# Digital.net
KiCad netlist of a schematic drawn in Altium Designer
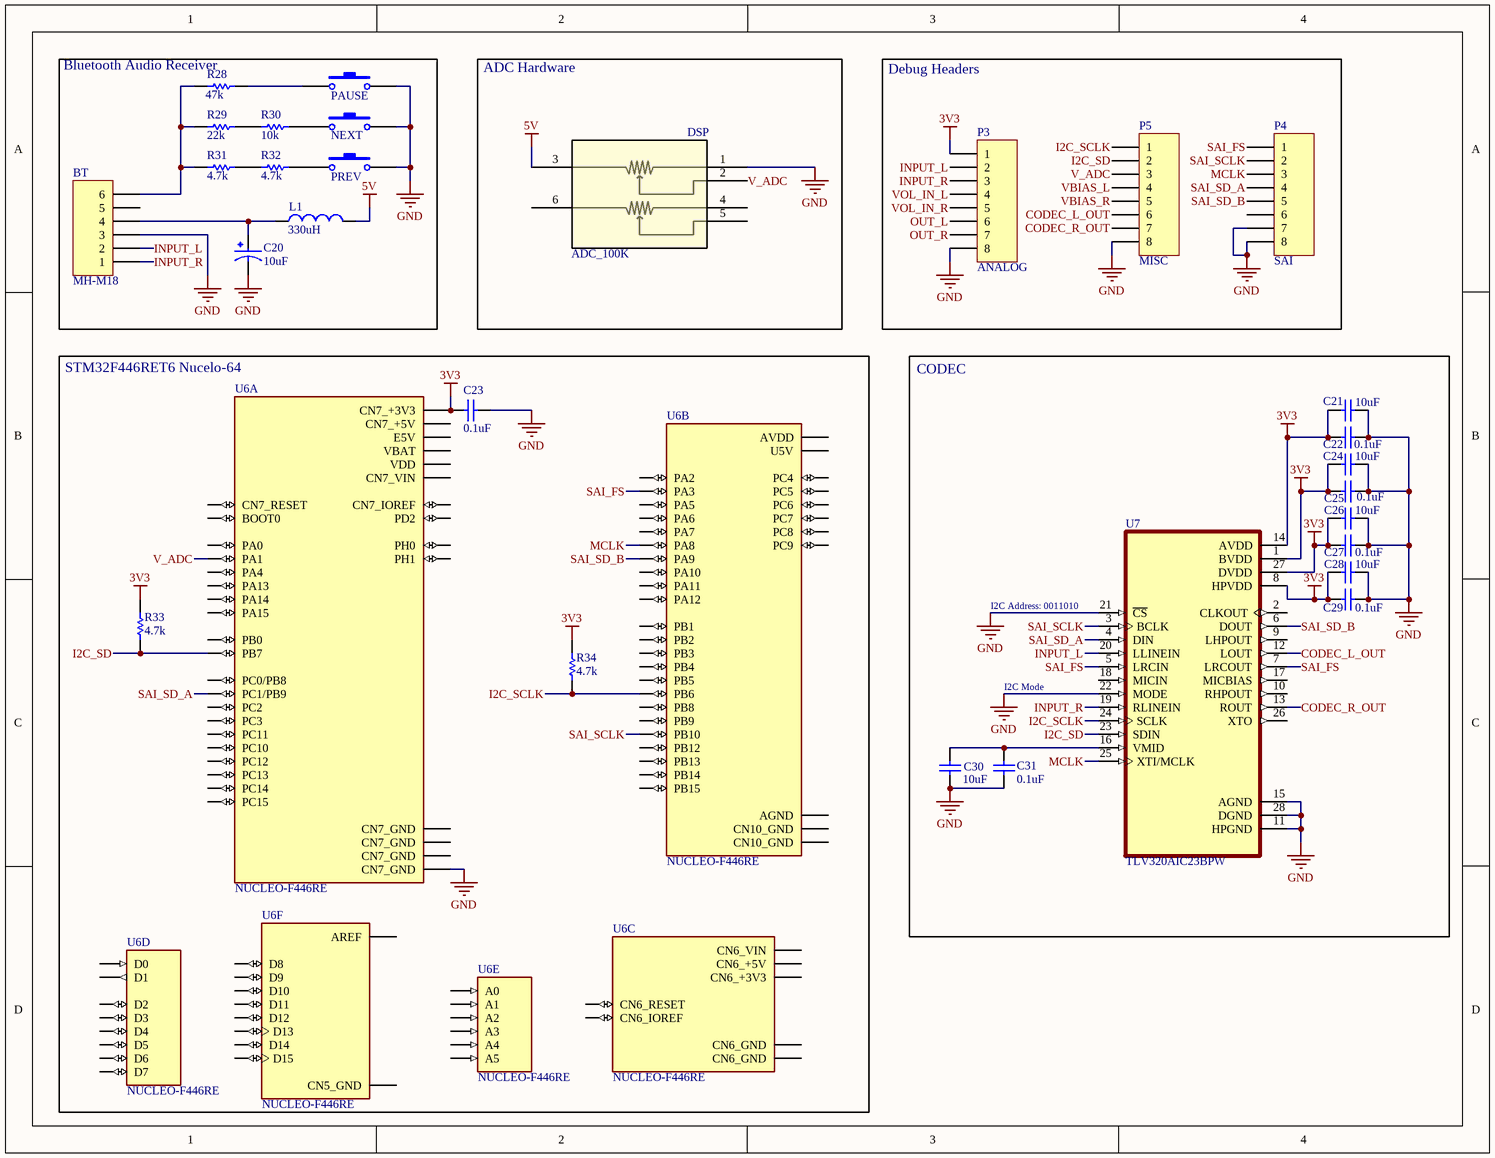
[diagram p0: Digital.SchDoc]

(export (version "E")
  (design (tool "Eeschema 10.0.6"))
  (components
    (comp (ref "BT")
      (value "MH-M18")
      (footprint "HDR1X6")
      (description "Header, 6-Pin")
      (fields (field (name "PUBLISHER") "Altium Limited"))
      (libsource (lib "Miscellaneous Connectors") (part "Header 6"))
    )
    (comp (ref "C20")
      (value "10uF")
      (footprint "CAPPRD200W50D500H1500")
      (description "Capacitor; Aluminum Electrolytic; Radial Al Electrolytic Cap; 100uF 63V")
      (fields (field (name "MF") "Panasonic Electronic") (field (name "MP") "EEU-FC1J101"))
      (libsource (lib "EEUFC1J101") (part "EEUFC1J101"))
    )
    (comp (ref "C21")
      (value "10uF")
      (footprint "RAD-0.1")
      (description "Capacitor")
      (fields (field (name "Comment") "Cap") (field (name "PUBLISHER") "Altium Limited"))
      (libsource (lib "Miscellaneous Devices") (part "Cap"))
    )
    (comp (ref "C22")
      (value "0.1uF")
      (footprint "RAD-0.1")
      (description "Capacitor")
      (fields (field (name "Comment") "Cap") (field (name "PUBLISHER") "Altium Limited"))
      (libsource (lib "Miscellaneous Devices") (part "Cap"))
    )
    (comp (ref "C23")
      (value "0.1uF")
      (footprint "RAD-0.1")
      (description "Capacitor")
      (fields (field (name "Comment") "Cap") (field (name "PUBLISHER") "Altium Limited"))
      (libsource (lib "Miscellaneous Devices") (part "Cap"))
    )
    (comp (ref "C24")
      (value "10uF")
      (footprint "RAD-0.1")
      (description "Capacitor")
      (fields (field (name "Comment") "Cap") (field (name "PUBLISHER") "Altium Limited"))
      (libsource (lib "Miscellaneous Devices") (part "Cap"))
    )
    (comp (ref "C25")
      (value "0.1uF")
      (footprint "RAD-0.1")
      (description "Capacitor")
      (fields (field (name "Comment") "Cap") (field (name "PUBLISHER") "Altium Limited"))
      (libsource (lib "Miscellaneous Devices") (part "Cap"))
    )
    (comp (ref "C26")
      (value "10uF")
      (footprint "RAD-0.1")
      (description "Capacitor")
      (fields (field (name "Comment") "Cap") (field (name "PUBLISHER") "Altium Limited"))
      (libsource (lib "Miscellaneous Devices") (part "Cap"))
    )
    (comp (ref "C27")
      (value "0.1uF")
      (footprint "RAD-0.1")
      (description "Capacitor")
      (fields (field (name "Comment") "Cap") (field (name "PUBLISHER") "Altium Limited"))
      (libsource (lib "Miscellaneous Devices") (part "Cap"))
    )
    (comp (ref "C28")
      (value "10uF")
      (footprint "RAD-0.1")
      (description "Capacitor")
      (fields (field (name "Comment") "Cap") (field (name "PUBLISHER") "Altium Limited"))
      (libsource (lib "Miscellaneous Devices") (part "Cap"))
    )
    (comp (ref "C29")
      (value "0.1uF")
      (footprint "RAD-0.1")
      (description "Capacitor")
      (fields (field (name "Comment") "Cap") (field (name "PUBLISHER") "Altium Limited"))
      (libsource (lib "Miscellaneous Devices") (part "Cap"))
    )
    (comp (ref "C30")
      (value "10uF")
      (footprint "RAD-0.1")
      (description "Capacitor")
      (fields (field (name "Comment") "Cap") (field (name "PUBLISHER") "Altium Limited"))
      (libsource (lib "Miscellaneous Devices") (part "Cap"))
    )
    (comp (ref "C31")
      (value "0.1uF")
      (footprint "RAD-0.1")
      (description "Capacitor")
      (fields (field (name "Comment") "Cap") (field (name "PUBLISHER") "Altium Limited"))
      (libsource (lib "Miscellaneous Devices") (part "Cap"))
    )
    (comp (ref "DSP")
      (value "ADC_100K")
      (footprint "Bourns_PDB182-K425K-103A_0")
      (description "No Description Available")
      (fields
        (field (name "MANUFACTURER_PART_NUMBER") "PDB182-K420K-103A2")
        (field (name "COPYRIGHT") "Copyright (C) 2022 Ultra Librarian. All rights reserved.")
      )
      (libsource (lib "PDB182-K420K-103A2") (part "PDB182-K420K-103A2"))
    )
    (comp (ref "L1")
      (value "330uH")
      (footprint "RAD-0.4")
      (description "Inductor")
      (fields (field (name "PUBLISHER") "Altium Limited"))
      (libsource (lib "Miscellaneous Devices") (part "Inductor"))
    )
    (comp (ref "NEXT")
      (value "NEXT")
      (footprint "SW PB")
      (description "Switch")
      (fields (field (name "PUBLISHER") "Altium Limited"))
      (libsource (lib "Miscellaneous Devices") (part "SW-PB"))
    )
    (comp (ref "P3")
      (value "ANALOG")
      (footprint "HDR1X8")
      (description "Header, 8-Pin")
      (fields (field (name "PUBLISHER") "Altium Limited"))
      (libsource (lib "Miscellaneous Connectors") (part "Header 8"))
    )
    (comp (ref "P4")
      (value "SAI")
      (footprint "HDR1X8")
      (description "Header, 8-Pin")
      (fields (field (name "PUBLISHER") "Altium Limited"))
      (libsource (lib "Miscellaneous Connectors") (part "Header 8"))
    )
    (comp (ref "P5")
      (value "MISC")
      (footprint "HDR1X8")
      (description "Header, 8-Pin")
      (fields (field (name "PUBLISHER") "Altium Limited"))
      (libsource (lib "Miscellaneous Connectors") (part "Header 8"))
    )
    (comp (ref "PAUSE")
      (value "PAUSE")
      (footprint "SW PB")
      (description "Switch")
      (fields (field (name "PUBLISHER") "Altium Limited"))
      (libsource (lib "Miscellaneous Devices") (part "SW-PB"))
    )
    (comp (ref "PREV")
      (value "PREV")
      (footprint "SW PB")
      (description "Switch")
      (fields (field (name "PUBLISHER") "Altium Limited"))
      (libsource (lib "Miscellaneous Devices") (part "SW-PB"))
    )
    (comp (ref "R28")
      (value "47k")
      (footprint "AXIAL-0.3")
      (description "Resistor")
      (fields (field (name "Comment") "Res1") (field (name "PUBLISHER") "Altium Limited"))
      (libsource (lib "Miscellaneous Devices") (part "Res1"))
    )
    (comp (ref "R29")
      (value "22k")
      (footprint "AXIAL-0.3")
      (description "Resistor")
      (fields (field (name "Comment") "Res1") (field (name "PUBLISHER") "Altium Limited"))
      (libsource (lib "Miscellaneous Devices") (part "Res1"))
    )
    (comp (ref "R30")
      (value "10k")
      (footprint "AXIAL-0.3")
      (description "Resistor")
      (fields (field (name "Comment") "Res1") (field (name "PUBLISHER") "Altium Limited"))
      (libsource (lib "Miscellaneous Devices") (part "Res1"))
    )
    (comp (ref "R31")
      (value "4.7k")
      (footprint "AXIAL-0.3")
      (description "Resistor")
      (fields (field (name "Comment") "Res1") (field (name "PUBLISHER") "Altium Limited"))
      (libsource (lib "Miscellaneous Devices") (part "Res1"))
    )
    (comp (ref "R32")
      (value "4.7k")
      (footprint "AXIAL-0.3")
      (description "Resistor")
      (fields (field (name "Comment") "Res1") (field (name "PUBLISHER") "Altium Limited"))
      (libsource (lib "Miscellaneous Devices") (part "Res1"))
    )
    (comp (ref "R33")
      (value "4.7k")
      (footprint "AXIAL-0.3")
      (description "Resistor")
      (fields (field (name "Comment") "Res1") (field (name "PUBLISHER") "Altium Limited"))
      (libsource (lib "Miscellaneous Devices") (part "Res1"))
    )
    (comp (ref "R34")
      (value "4.7k")
      (footprint "AXIAL-0.3")
      (description "Resistor")
      (fields (field (name "Comment") "Res1") (field (name "PUBLISHER") "Altium Limited"))
      (libsource (lib "Miscellaneous Devices") (part "Res1"))
    )
    (comp (ref "U6")
      (value "NUCLEO-F446RE")
      (footprint "MODULE_NUCLEO-F446RE")
      (libsource (lib "NUCLEO-F446RE") (part "NUCLEO-F446RE"))
    )
    (comp (ref "U7")
      (value "TLV320AIC23BPW")
      (footprint "SOP65P640X120-28N")
      (description "Low-Power Stereo CODEC with HP Amplifier 28-TSSOP -10 to 70")
      (fields (field (name "MF") "Texas Instruments"))
      (libsource (lib "TLV320AIC23BPW") (part "TLV320AIC23BPW"))
    )
  )
  (nets
    (net (code "1") (name "/CODEC_L_OUT") (class "Default")
      (node (ref "P5") (pin "6") (pinfunction "6_6") (pintype "passive"))
      (node (ref "U7") (pin "12") (pinfunction "LOUT_12") (pintype "output"))
    )
    (net (code "2") (name "/CODEC_R_OUT") (class "Default")
      (node (ref "P5") (pin "7") (pinfunction "7_7") (pintype "passive"))
      (node (ref "U7") (pin "13") (pinfunction "ROUT_13") (pintype "output"))
    )
    (net (code "3") (name "/I2C_SCLK") (class "Default")
      (node (ref "P5") (pin "1") (pinfunction "1_1") (pintype "passive"))
      (node (ref "R34") (pin "1") (pinfunction "1_1") (pintype "passive"))
      (node (ref "U6") (pin "CN10_17") (pinfunction "PB6_CN10_17") (pintype "bidirectional"))
      (node (ref "U7") (pin "24") (pinfunction "SCLK_24") (pintype "input"))
    )
    (net (code "4") (name "/I2C_SD") (class "Default")
      (node (ref "P5") (pin "2") (pinfunction "2_2") (pintype "passive"))
      (node (ref "R33") (pin "1") (pinfunction "1_1") (pintype "passive"))
      (node (ref "U6") (pin "CN7_21") (pinfunction "PB7_CN7_21") (pintype "bidirectional"))
      (node (ref "U7") (pin "23") (pinfunction "SDIN_23") (pintype "input"))
    )
    (net (code "5") (name "/INPUT_L") (class "Default")
      (node (ref "BT") (pin "2") (pinfunction "2_2") (pintype "passive"))
      (node (ref "P3") (pin "2") (pinfunction "2_2") (pintype "passive"))
      (node (ref "U7") (pin "20") (pinfunction "LLINEIN_20") (pintype "input"))
    )
    (net (code "6") (name "/INPUT_R") (class "Default")
      (node (ref "BT") (pin "1") (pinfunction "1_1") (pintype "passive"))
      (node (ref "P3") (pin "3") (pinfunction "3_3") (pintype "passive"))
      (node (ref "U7") (pin "19") (pinfunction "RLINEIN_19") (pintype "input"))
    )
    (net (code "7") (name "/MCLK") (class "Default")
      (node (ref "P4") (pin "3") (pinfunction "3_3") (pintype "passive"))
      (node (ref "U6") (pin "CN10_23") (pinfunction "PA8_CN10_23") (pintype "bidirectional"))
      (node (ref "U7") (pin "25") (pinfunction "XTI/MCLK_25") (pintype "input"))
    )
    (net (code "8") (name "/OUT_L") (class "Default")
      (node (ref "P3") (pin "6") (pinfunction "6_6") (pintype "passive"))
    )
    (net (code "9") (name "/OUT_R") (class "Default")
      (node (ref "P3") (pin "7") (pinfunction "7_7") (pintype "passive"))
    )
    (net (code "10") (name "/SAI_FS") (class "Default")
      (node (ref "P4") (pin "1") (pinfunction "1_1") (pintype "passive"))
      (node (ref "U6") (pin "CN10_37") (pinfunction "PA3_CN10_37") (pintype "bidirectional"))
      (node (ref "U7") (pin "5") (pinfunction "LRCIN_5") (pintype "input"))
      (node (ref "U7") (pin "7") (pinfunction "LRCOUT_7") (pintype "output"))
    )
    (net (code "11") (name "/SAI_SCLK") (class "Default")
      (node (ref "P4") (pin "2") (pinfunction "2_2") (pintype "passive"))
      (node (ref "U6") (pin "CN10_25") (pinfunction "PB10_CN10_25") (pintype "bidirectional"))
      (node (ref "U7") (pin "3") (pinfunction "BCLK_3") (pintype "input"))
    )
    (net (code "12") (name "/SAI_SD_A") (class "Default")
      (node (ref "P4") (pin "4") (pinfunction "4_4") (pintype "passive"))
      (node (ref "U6") (pin "CN7_36") (pinfunction "PC1/PB9_CN7_36") (pintype "bidirectional"))
      (node (ref "U7") (pin "4") (pinfunction "DIN_4") (pintype "input"))
    )
    (net (code "13") (name "/SAI_SD_B") (class "Default")
      (node (ref "P4") (pin "5") (pinfunction "5_5") (pintype "passive"))
      (node (ref "U6") (pin "CN10_21") (pinfunction "PA9_CN10_21") (pintype "bidirectional"))
      (node (ref "U7") (pin "6") (pinfunction "DOUT_6") (pintype "output"))
    )
    (net (code "14") (name "/VBIAS_L") (class "Default")
      (node (ref "P5") (pin "4") (pinfunction "4_4") (pintype "passive"))
    )
    (net (code "15") (name "/VBIAS_R") (class "Default")
      (node (ref "P5") (pin "5") (pinfunction "5_5") (pintype "passive"))
    )
    (net (code "16") (name "/VOL_IN_L") (class "Default")
      (node (ref "P3") (pin "4") (pinfunction "4_4") (pintype "passive"))
    )
    (net (code "17") (name "/VOL_IN_R") (class "Default")
      (node (ref "P3") (pin "5") (pinfunction "5_5") (pintype "passive"))
    )
    (net (code "18") (name "/V_ADC") (class "Default")
      (node (ref "DSP") (pin "2") (pinfunction "2_2") (pintype "passive"))
      (node (ref "P5") (pin "3") (pinfunction "3_3") (pintype "passive"))
      (node (ref "U6") (pin "CN7_30") (pinfunction "PA1_CN7_30") (pintype "bidirectional"))
    )
    (net (code "19") (name "3V3") (class "Default")
      (node (ref "C21") (pin "1") (pinfunction "1_1") (pintype "passive"))
      (node (ref "C22") (pin "1") (pinfunction "1_1") (pintype "passive"))
      (node (ref "C23") (pin "1") (pinfunction "1_1") (pintype "passive"))
      (node (ref "C24") (pin "1") (pinfunction "1_1") (pintype "passive"))
      (node (ref "C25") (pin "1") (pinfunction "1_1") (pintype "passive"))
      (node (ref "C26") (pin "1") (pinfunction "1_1") (pintype "passive"))
      (node (ref "C27") (pin "2") (pinfunction "2_2") (pintype "passive"))
      (node (ref "C28") (pin "1") (pinfunction "1_1") (pintype "passive"))
      (node (ref "C29") (pin "2") (pinfunction "2_2") (pintype "passive"))
      (node (ref "P3") (pin "1") (pinfunction "1_1") (pintype "passive"))
      (node (ref "R33") (pin "2") (pinfunction "2_2") (pintype "passive"))
      (node (ref "R34") (pin "2") (pinfunction "2_2") (pintype "passive"))
      (node (ref "U6") (pin "CN7_16") (pinfunction "CN7_+3V3_CN7_16") (pintype "power_in"))
      (node (ref "U7") (pin "1") (pinfunction "BVDD_1") (pintype "power_in"))
      (node (ref "U7") (pin "14") (pinfunction "AVDD_14") (pintype "power_in"))
      (node (ref "U7") (pin "27") (pinfunction "DVDD_27") (pintype "power_in"))
      (node (ref "U7") (pin "8") (pinfunction "HPVDD_8") (pintype "power_in"))
    )
    (net (code "20") (name "5V") (class "Default")
      (node (ref "DSP") (pin "3") (pinfunction "1_3") (pintype "passive"))
      (node (ref "L1") (pin "2") (pinfunction "2_2") (pintype "passive"))
    )
    (net (code "21") (name "GND") (class "Default")
      (node (ref "BT") (pin "3") (pinfunction "3_3") (pintype "passive"))
      (node (ref "C20") (pin "N") (pinfunction "N_N") (pintype "passive"))
      (node (ref "C21") (pin "2") (pinfunction "2_2") (pintype "passive"))
      (node (ref "C22") (pin "2") (pinfunction "2_2") (pintype "passive"))
      (node (ref "C23") (pin "2") (pinfunction "2_2") (pintype "passive"))
      (node (ref "C24") (pin "2") (pinfunction "2_2") (pintype "passive"))
      (node (ref "C25") (pin "2") (pinfunction "2_2") (pintype "passive"))
      (node (ref "C26") (pin "2") (pinfunction "2_2") (pintype "passive"))
      (node (ref "C27") (pin "1") (pinfunction "1_1") (pintype "passive"))
      (node (ref "C28") (pin "2") (pinfunction "2_2") (pintype "passive"))
      (node (ref "C29") (pin "1") (pinfunction "1_1") (pintype "passive"))
      (node (ref "C30") (pin "1") (pinfunction "1_1") (pintype "passive"))
      (node (ref "C31") (pin "1") (pinfunction "1_1") (pintype "passive"))
      (node (ref "DSP") (pin "1") (pinfunction "3_1") (pintype "passive"))
      (node (ref "NEXT") (pin "2") (pinfunction "2_2") (pintype "passive"))
      (node (ref "P3") (pin "8") (pinfunction "8_8") (pintype "passive"))
      (node (ref "P4") (pin "7") (pinfunction "7_7") (pintype "passive"))
      (node (ref "P4") (pin "8") (pinfunction "8_8") (pintype "passive"))
      (node (ref "P5") (pin "8") (pinfunction "8_8") (pintype "passive"))
      (node (ref "PAUSE") (pin "2") (pinfunction "2_2") (pintype "passive"))
      (node (ref "PREV") (pin "2") (pinfunction "2_2") (pintype "passive"))
      (node (ref "U6") (pin "CN7_22") (pinfunction "CN7_GND_CN7_22") (pintype "power_in"))
      (node (ref "U7") (pin "11") (pinfunction "HPGND_11") (pintype "power_in"))
      (node (ref "U7") (pin "15") (pinfunction "AGND_15") (pintype "power_in"))
      (node (ref "U7") (pin "21") (pinfunction "~{CS}_21") (pintype "input"))
      (node (ref "U7") (pin "22") (pinfunction "MODE_22") (pintype "input"))
      (node (ref "U7") (pin "28") (pinfunction "DGND_28") (pintype "power_in"))
    )
    (net (code "22") (name "Net-(BT-Pad4)") (class "Default")
      (node (ref "BT") (pin "4") (pinfunction "4_4") (pintype "passive"))
      (node (ref "C20") (pin "P") (pinfunction "P_P") (pintype "passive"))
      (node (ref "L1") (pin "1") (pinfunction "1_1") (pintype "passive"))
    )
    (net (code "23") (name "Net-(BT-Pad6)") (class "Default")
      (node (ref "BT") (pin "6") (pinfunction "6_6") (pintype "passive"))
      (node (ref "R28") (pin "1") (pinfunction "1_1") (pintype "passive"))
      (node (ref "R29") (pin "1") (pinfunction "1_1") (pintype "passive"))
      (node (ref "R31") (pin "1") (pinfunction "1_1") (pintype "passive"))
    )
    (net (code "24") (name "Net-(NEXT-Pad1)") (class "Default")
      (node (ref "NEXT") (pin "1") (pinfunction "1_1") (pintype "passive"))
      (node (ref "R30") (pin "2") (pinfunction "2_2") (pintype "passive"))
    )
    (net (code "25") (name "Net-(PAUSE-Pad1)") (class "Default")
      (node (ref "PAUSE") (pin "1") (pinfunction "1_1") (pintype "passive"))
      (node (ref "R28") (pin "2") (pinfunction "2_2") (pintype "passive"))
    )
    (net (code "26") (name "Net-(PREV-Pad1)") (class "Default")
      (node (ref "PREV") (pin "1") (pinfunction "1_1") (pintype "passive"))
      (node (ref "R32") (pin "2") (pinfunction "2_2") (pintype "passive"))
    )
    (net (code "27") (name "Net-(R29-Pad2)") (class "Default")
      (node (ref "R29") (pin "2") (pinfunction "2_2") (pintype "passive"))
      (node (ref "R30") (pin "1") (pinfunction "1_1") (pintype "passive"))
    )
    (net (code "28") (name "Net-(R31-Pad2)") (class "Default")
      (node (ref "R31") (pin "2") (pinfunction "2_2") (pintype "passive"))
      (node (ref "R32") (pin "1") (pinfunction "1_1") (pintype "passive"))
    )
    (net (code "29") (name "Net-(U7-VMID)") (class "Default")
      (node (ref "C30") (pin "2") (pinfunction "2_2") (pintype "passive"))
      (node (ref "C31") (pin "2") (pinfunction "2_2") (pintype "passive"))
      (node (ref "U7") (pin "16") (pinfunction "VMID_16") (pintype "input"))
    )
    (net (code "30") (name "unconnected-(BT-Pad5)") (class "Default")
      (node (ref "BT") (pin "5") (pinfunction "5_5") (pintype "passive"))
    )
    (net (code "31") (name "unconnected-(DSP-4-Pad6)") (class "Default")
      (node (ref "DSP") (pin "6") (pinfunction "4_6") (pintype "passive"))
    )
    (net (code "32") (name "unconnected-(DSP-6-Pad4)") (class "Default")
      (node (ref "DSP") (pin "4") (pinfunction "6_4") (pintype "passive"))
    )
    (net (code "33") (name "unconnected-(DSP-Pad5)") (class "Default")
      (node (ref "DSP") (pin "5") (pinfunction "5_5") (pintype "passive"))
    )
    (net (code "34") (name "unconnected-(P4-Pad6)") (class "Default")
      (node (ref "P4") (pin "6") (pinfunction "6_6") (pintype "passive"))
    )
    (net (code "35") (name "unconnected-(U6A-BOOT0-PadCN7_7)") (class "Default")
      (node (ref "U6") (pin "CN7_7") (pinfunction "BOOT0_CN7_7") (pintype "bidirectional"))
    )
    (net (code "36") (name "unconnected-(U6A-CN7_+5V-PadCN7_18)") (class "Default")
      (node (ref "U6") (pin "CN7_18") (pinfunction "CN7_+5V_CN7_18") (pintype "power_in"))
    )
    (net (code "37") (name "unconnected-(U6A-CN7_GND-PadCN7_8)") (class "Default")
      (node (ref "U6") (pin "CN7_8") (pinfunction "CN7_GND_CN7_8") (pintype "power_in"))
    )
    (net (code "38") (name "unconnected-(U6A-CN7_GND-PadCN7_19)") (class "Default")
      (node (ref "U6") (pin "CN7_19") (pinfunction "CN7_GND_CN7_19") (pintype "power_in"))
    )
    (net (code "39") (name "unconnected-(U6A-CN7_GND-PadCN7_20)") (class "Default")
      (node (ref "U6") (pin "CN7_20") (pinfunction "CN7_GND_CN7_20") (pintype "power_in"))
    )
    (net (code "40") (name "unconnected-(U6A-CN7_IOREF-PadCN7_12)") (class "Default")
      (node (ref "U6") (pin "CN7_12") (pinfunction "CN7_IOREF_CN7_12") (pintype "bidirectional"))
    )
    (net (code "41") (name "unconnected-(U6A-CN7_RESET-PadCN7_14)") (class "Default")
      (node (ref "U6") (pin "CN7_14") (pinfunction "CN7_RESET_CN7_14") (pintype "bidirectional"))
    )
    (net (code "42") (name "unconnected-(U6A-CN7_VIN-PadCN7_24)") (class "Default")
      (node (ref "U6") (pin "CN7_24") (pinfunction "CN7_VIN_CN7_24") (pintype "power_in"))
    )
    (net (code "43") (name "unconnected-(U6A-E5V-PadCN7_6)") (class "Default")
      (node (ref "U6") (pin "CN7_6") (pinfunction "E5V_CN7_6") (pintype "power_in"))
    )
    (net (code "44") (name "unconnected-(U6A-PA0-PadCN7_28)") (class "Default")
      (node (ref "U6") (pin "CN7_28") (pinfunction "PA0_CN7_28") (pintype "bidirectional"))
    )
    (net (code "45") (name "unconnected-(U6A-PA4-PadCN7_32)") (class "Default")
      (node (ref "U6") (pin "CN7_32") (pinfunction "PA4_CN7_32") (pintype "bidirectional"))
    )
    (net (code "46") (name "unconnected-(U6A-PA13-PadCN7_13)") (class "Default")
      (node (ref "U6") (pin "CN7_13") (pinfunction "PA13_CN7_13") (pintype "bidirectional"))
    )
    (net (code "47") (name "unconnected-(U6A-PA14-PadCN7_15)") (class "Default")
      (node (ref "U6") (pin "CN7_15") (pinfunction "PA14_CN7_15") (pintype "bidirectional"))
    )
    (net (code "48") (name "unconnected-(U6A-PA15-PadCN7_17)") (class "Default")
      (node (ref "U6") (pin "CN7_17") (pinfunction "PA15_CN7_17") (pintype "bidirectional"))
    )
    (net (code "49") (name "unconnected-(U6A-PB0-PadCN7_34)") (class "Default")
      (node (ref "U6") (pin "CN7_34") (pinfunction "PB0_CN7_34") (pintype "bidirectional"))
    )
    (net (code "50") (name "unconnected-(U6A-PC0{slash}PB8-PadCN7_38)") (class "Default")
      (node (ref "U6") (pin "CN7_38") (pinfunction "PC0/PB8_CN7_38") (pintype "bidirectional"))
    )
    (net (code "51") (name "unconnected-(U6A-PC2-PadCN7_35)") (class "Default")
      (node (ref "U6") (pin "CN7_35") (pinfunction "PC2_CN7_35") (pintype "bidirectional"))
    )
    (net (code "52") (name "unconnected-(U6A-PC3-PadCN7_37)") (class "Default")
      (node (ref "U6") (pin "CN7_37") (pinfunction "PC3_CN7_37") (pintype "bidirectional"))
    )
    (net (code "53") (name "unconnected-(U6A-PC10-PadCN7_1)") (class "Default")
      (node (ref "U6") (pin "CN7_1") (pinfunction "PC10_CN7_1") (pintype "bidirectional"))
    )
    (net (code "54") (name "unconnected-(U6A-PC11-PadCN7_2)") (class "Default")
      (node (ref "U6") (pin "CN7_2") (pinfunction "PC11_CN7_2") (pintype "bidirectional"))
    )
    (net (code "55") (name "unconnected-(U6A-PC12-PadCN7_3)") (class "Default")
      (node (ref "U6") (pin "CN7_3") (pinfunction "PC12_CN7_3") (pintype "bidirectional"))
    )
    (net (code "56") (name "unconnected-(U6A-PC13-PadCN7_23)") (class "Default")
      (node (ref "U6") (pin "CN7_23") (pinfunction "PC13_CN7_23") (pintype "bidirectional"))
    )
    (net (code "57") (name "unconnected-(U6A-PC14-PadCN7_25)") (class "Default")
      (node (ref "U6") (pin "CN7_25") (pinfunction "PC14_CN7_25") (pintype "bidirectional"))
    )
    (net (code "58") (name "unconnected-(U6A-PC15-PadCN7_27)") (class "Default")
      (node (ref "U6") (pin "CN7_27") (pinfunction "PC15_CN7_27") (pintype "bidirectional"))
    )
    (net (code "59") (name "unconnected-(U6A-PD2-PadCN7_4)") (class "Default")
      (node (ref "U6") (pin "CN7_4") (pinfunction "PD2_CN7_4") (pintype "bidirectional"))
    )
    (net (code "60") (name "unconnected-(U6A-PH0-PadCN7_29)") (class "Default")
      (node (ref "U6") (pin "CN7_29") (pinfunction "PH0_CN7_29") (pintype "bidirectional"))
    )
    (net (code "61") (name "unconnected-(U6A-PH1-PadCN7_31)") (class "Default")
      (node (ref "U6") (pin "CN7_31") (pinfunction "PH1_CN7_31") (pintype "bidirectional"))
    )
    (net (code "62") (name "unconnected-(U6A-VBAT-PadCN7_33)") (class "Default")
      (node (ref "U6") (pin "CN7_33") (pinfunction "VBAT_CN7_33") (pintype "power_in"))
    )
    (net (code "63") (name "unconnected-(U6A-VDD-PadCN7_5)") (class "Default")
      (node (ref "U6") (pin "CN7_5") (pinfunction "VDD_CN7_5") (pintype "power_in"))
    )
    (net (code "64") (name "unconnected-(U6B-AGND-PadCN10_32)") (class "Default")
      (node (ref "U6") (pin "CN10_32") (pinfunction "AGND_CN10_32") (pintype "power_in"))
    )
    (net (code "65") (name "unconnected-(U6B-AVDD-PadCN10_7)") (class "Default")
      (node (ref "U6") (pin "CN10_7") (pinfunction "AVDD_CN10_7") (pintype "power_in"))
    )
    (net (code "66") (name "unconnected-(U6B-CN10_GND-PadCN10_9)") (class "Default")
      (node (ref "U6") (pin "CN10_9") (pinfunction "CN10_GND_CN10_9") (pintype "power_in"))
    )
    (net (code "67") (name "unconnected-(U6B-CN10_GND-PadCN10_20)") (class "Default")
      (node (ref "U6") (pin "CN10_20") (pinfunction "CN10_GND_CN10_20") (pintype "power_in"))
    )
    (net (code "68") (name "unconnected-(U6B-PA2-PadCN10_35)") (class "Default")
      (node (ref "U6") (pin "CN10_35") (pinfunction "PA2_CN10_35") (pintype "bidirectional"))
    )
    (net (code "69") (name "unconnected-(U6B-PA5-PadCN10_11)") (class "Default")
      (node (ref "U6") (pin "CN10_11") (pinfunction "PA5_CN10_11") (pintype "bidirectional"))
    )
    (net (code "70") (name "unconnected-(U6B-PA6-PadCN10_13)") (class "Default")
      (node (ref "U6") (pin "CN10_13") (pinfunction "PA6_CN10_13") (pintype "bidirectional"))
    )
    (net (code "71") (name "unconnected-(U6B-PA7-PadCN10_15)") (class "Default")
      (node (ref "U6") (pin "CN10_15") (pinfunction "PA7_CN10_15") (pintype "bidirectional"))
    )
    (net (code "72") (name "unconnected-(U6B-PA10-PadCN10_33)") (class "Default")
      (node (ref "U6") (pin "CN10_33") (pinfunction "PA10_CN10_33") (pintype "bidirectional"))
    )
    (net (code "73") (name "unconnected-(U6B-PA11-PadCN10_14)") (class "Default")
      (node (ref "U6") (pin "CN10_14") (pinfunction "PA11_CN10_14") (pintype "bidirectional"))
    )
    (net (code "74") (name "unconnected-(U6B-PA12-PadCN10_12)") (class "Default")
      (node (ref "U6") (pin "CN10_12") (pinfunction "PA12_CN10_12") (pintype "bidirectional"))
    )
    (net (code "75") (name "unconnected-(U6B-PB1-PadCN10_24)") (class "Default")
      (node (ref "U6") (pin "CN10_24") (pinfunction "PB1_CN10_24") (pintype "bidirectional"))
    )
    (net (code "76") (name "unconnected-(U6B-PB2-PadCN10_22)") (class "Default")
      (node (ref "U6") (pin "CN10_22") (pinfunction "PB2_CN10_22") (pintype "bidirectional"))
    )
    (net (code "77") (name "unconnected-(U6B-PB3-PadCN10_31)") (class "Default")
      (node (ref "U6") (pin "CN10_31") (pinfunction "PB3_CN10_31") (pintype "bidirectional"))
    )
    (net (code "78") (name "unconnected-(U6B-PB4-PadCN10_27)") (class "Default")
      (node (ref "U6") (pin "CN10_27") (pinfunction "PB4_CN10_27") (pintype "bidirectional"))
    )
    (net (code "79") (name "unconnected-(U6B-PB5-PadCN10_29)") (class "Default")
      (node (ref "U6") (pin "CN10_29") (pinfunction "PB5_CN10_29") (pintype "bidirectional"))
    )
    (net (code "80") (name "unconnected-(U6B-PB8-PadCN10_3)") (class "Default")
      (node (ref "U6") (pin "CN10_3") (pinfunction "PB8_CN10_3") (pintype "bidirectional"))
    )
    (net (code "81") (name "unconnected-(U6B-PB9-PadCN10_5)") (class "Default")
      (node (ref "U6") (pin "CN10_5") (pinfunction "PB9_CN10_5") (pintype "bidirectional"))
    )
    (net (code "82") (name "unconnected-(U6B-PB12-PadCN10_16)") (class "Default")
      (node (ref "U6") (pin "CN10_16") (pinfunction "PB12_CN10_16") (pintype "bidirectional"))
    )
    (net (code "83") (name "unconnected-(U6B-PB13-PadCN10_30)") (class "Default")
      (node (ref "U6") (pin "CN10_30") (pinfunction "PB13_CN10_30") (pintype "bidirectional"))
    )
    (net (code "84") (name "unconnected-(U6B-PB14-PadCN10_28)") (class "Default")
      (node (ref "U6") (pin "CN10_28") (pinfunction "PB14_CN10_28") (pintype "bidirectional"))
    )
    (net (code "85") (name "unconnected-(U6B-PB15-PadCN10_26)") (class "Default")
      (node (ref "U6") (pin "CN10_26") (pinfunction "PB15_CN10_26") (pintype "bidirectional"))
    )
    (net (code "86") (name "unconnected-(U6B-PC4-PadCN10_34)") (class "Default")
      (node (ref "U6") (pin "CN10_34") (pinfunction "PC4_CN10_34") (pintype "bidirectional"))
    )
    (net (code "87") (name "unconnected-(U6B-PC5-PadCN10_6)") (class "Default")
      (node (ref "U6") (pin "CN10_6") (pinfunction "PC5_CN10_6") (pintype "bidirectional"))
    )
    (net (code "88") (name "unconnected-(U6B-PC6-PadCN10_4)") (class "Default")
      (node (ref "U6") (pin "CN10_4") (pinfunction "PC6_CN10_4") (pintype "bidirectional"))
    )
    (net (code "89") (name "unconnected-(U6B-PC7-PadCN10_19)") (class "Default")
      (node (ref "U6") (pin "CN10_19") (pinfunction "PC7_CN10_19") (pintype "bidirectional"))
    )
    (net (code "90") (name "unconnected-(U6B-PC8-PadCN10_2)") (class "Default")
      (node (ref "U6") (pin "CN10_2") (pinfunction "PC8_CN10_2") (pintype "bidirectional"))
    )
    (net (code "91") (name "unconnected-(U6B-PC9-PadCN10_1)") (class "Default")
      (node (ref "U6") (pin "CN10_1") (pinfunction "PC9_CN10_1") (pintype "bidirectional"))
    )
    (net (code "92") (name "unconnected-(U6B-U5V-PadCN10_8)") (class "Default")
      (node (ref "U6") (pin "CN10_8") (pinfunction "U5V_CN10_8") (pintype "power_in"))
    )
    (net (code "93") (name "unconnected-(U6C-CN6_+3V3-PadCN6_4)") (class "Default")
      (node (ref "U6") (pin "CN6_4") (pinfunction "CN6_+3V3_CN6_4") (pintype "power_in"))
    )
    (net (code "94") (name "unconnected-(U6C-CN6_+5V-PadCN6_5)") (class "Default")
      (node (ref "U6") (pin "CN6_5") (pinfunction "CN6_+5V_CN6_5") (pintype "power_in"))
    )
    (net (code "95") (name "unconnected-(U6C-CN6_GND-PadCN6_6)") (class "Default")
      (node (ref "U6") (pin "CN6_6") (pinfunction "CN6_GND_CN6_6") (pintype "power_in"))
    )
    (net (code "96") (name "unconnected-(U6C-CN6_GND-PadCN6_7)") (class "Default")
      (node (ref "U6") (pin "CN6_7") (pinfunction "CN6_GND_CN6_7") (pintype "power_in"))
    )
    (net (code "97") (name "unconnected-(U6C-CN6_IOREF-PadCN6_2)") (class "Default")
      (node (ref "U6") (pin "CN6_2") (pinfunction "CN6_IOREF_CN6_2") (pintype "bidirectional"))
    )
    (net (code "98") (name "unconnected-(U6C-CN6_RESET-PadCN6_3)") (class "Default")
      (node (ref "U6") (pin "CN6_3") (pinfunction "CN6_RESET_CN6_3") (pintype "bidirectional"))
    )
    (net (code "99") (name "unconnected-(U6C-CN6_VIN-PadCN6_8)") (class "Default")
      (node (ref "U6") (pin "CN6_8") (pinfunction "CN6_VIN_CN6_8") (pintype "power_in"))
    )
    (net (code "100") (name "unconnected-(U6D-D0-PadCN9_1)") (class "Default")
      (node (ref "U6") (pin "CN9_1") (pinfunction "D0_CN9_1") (pintype "input"))
    )
    (net (code "101") (name "unconnected-(U6D-D1-PadCN9_2)") (class "Default")
      (node (ref "U6") (pin "CN9_2") (pinfunction "D1_CN9_2") (pintype "output"))
    )
    (net (code "102") (name "unconnected-(U6D-D2-PadCN9_3)") (class "Default")
      (node (ref "U6") (pin "CN9_3") (pinfunction "D2_CN9_3") (pintype "bidirectional"))
    )
    (net (code "103") (name "unconnected-(U6D-D3-PadCN9_4)") (class "Default")
      (node (ref "U6") (pin "CN9_4") (pinfunction "D3_CN9_4") (pintype "bidirectional"))
    )
    (net (code "104") (name "unconnected-(U6D-D4-PadCN9_5)") (class "Default")
      (node (ref "U6") (pin "CN9_5") (pinfunction "D4_CN9_5") (pintype "bidirectional"))
    )
    (net (code "105") (name "unconnected-(U6D-D5-PadCN9_6)") (class "Default")
      (node (ref "U6") (pin "CN9_6") (pinfunction "D5_CN9_6") (pintype "bidirectional"))
    )
    (net (code "106") (name "unconnected-(U6D-D6-PadCN9_7)") (class "Default")
      (node (ref "U6") (pin "CN9_7") (pinfunction "D6_CN9_7") (pintype "bidirectional"))
    )
    (net (code "107") (name "unconnected-(U6D-D7-PadCN9_8)") (class "Default")
      (node (ref "U6") (pin "CN9_8") (pinfunction "D7_CN9_8") (pintype "bidirectional"))
    )
    (net (code "108") (name "unconnected-(U6E-A0-PadCN8_1)") (class "Default")
      (node (ref "U6") (pin "CN8_1") (pinfunction "A0_CN8_1") (pintype "input"))
    )
    (net (code "109") (name "unconnected-(U6E-A1-PadCN8_2)") (class "Default")
      (node (ref "U6") (pin "CN8_2") (pinfunction "A1_CN8_2") (pintype "input"))
    )
    (net (code "110") (name "unconnected-(U6E-A2-PadCN8_3)") (class "Default")
      (node (ref "U6") (pin "CN8_3") (pinfunction "A2_CN8_3") (pintype "input"))
    )
    (net (code "111") (name "unconnected-(U6E-A3-PadCN8_4)") (class "Default")
      (node (ref "U6") (pin "CN8_4") (pinfunction "A3_CN8_4") (pintype "input"))
    )
    (net (code "112") (name "unconnected-(U6E-A4-PadCN8_5)") (class "Default")
      (node (ref "U6") (pin "CN8_5") (pinfunction "A4_CN8_5") (pintype "input"))
    )
    (net (code "113") (name "unconnected-(U6E-A5-PadCN8_6)") (class "Default")
      (node (ref "U6") (pin "CN8_6") (pinfunction "A5_CN8_6") (pintype "input"))
    )
    (net (code "114") (name "unconnected-(U6F-AREF-PadCN5_8)") (class "Default")
      (node (ref "U6") (pin "CN5_8") (pinfunction "AREF_CN5_8") (pintype "power_in"))
    )
    (net (code "115") (name "unconnected-(U6F-CN5_GND-PadCN5_7)") (class "Default")
      (node (ref "U6") (pin "CN5_7") (pinfunction "CN5_GND_CN5_7") (pintype "power_in"))
    )
    (net (code "116") (name "unconnected-(U6F-D8-PadCN5_1)") (class "Default")
      (node (ref "U6") (pin "CN5_1") (pinfunction "D8_CN5_1") (pintype "bidirectional"))
    )
    (net (code "117") (name "unconnected-(U6F-D9-PadCN5_2)") (class "Default")
      (node (ref "U6") (pin "CN5_2") (pinfunction "D9_CN5_2") (pintype "bidirectional"))
    )
    (net (code "118") (name "unconnected-(U6F-D10-PadCN5_3)") (class "Default")
      (node (ref "U6") (pin "CN5_3") (pinfunction "D10_CN5_3") (pintype "bidirectional"))
    )
    (net (code "119") (name "unconnected-(U6F-D11-PadCN5_4)") (class "Default")
      (node (ref "U6") (pin "CN5_4") (pinfunction "D11_CN5_4") (pintype "bidirectional"))
    )
    (net (code "120") (name "unconnected-(U6F-D12-PadCN5_5)") (class "Default")
      (node (ref "U6") (pin "CN5_5") (pinfunction "D12_CN5_5") (pintype "bidirectional"))
    )
    (net (code "121") (name "unconnected-(U6F-D13-PadCN5_6)") (class "Default")
      (node (ref "U6") (pin "CN5_6") (pinfunction "D13_CN5_6") (pintype "bidirectional"))
    )
    (net (code "122") (name "unconnected-(U6F-D14-PadCN5_9)") (class "Default")
      (node (ref "U6") (pin "CN5_9") (pinfunction "D14_CN5_9") (pintype "bidirectional"))
    )
    (net (code "123") (name "unconnected-(U6F-D15-PadCN5_10)") (class "Default")
      (node (ref "U6") (pin "CN5_10") (pinfunction "D15_CN5_10") (pintype "bidirectional"))
    )
    (net (code "124") (name "unconnected-(U7-CLKOUT-Pad2)") (class "Default")
      (node (ref "U7") (pin "2") (pinfunction "CLKOUT_2") (pintype "output"))
    )
    (net (code "125") (name "unconnected-(U7-LHPOUT-Pad9)") (class "Default")
      (node (ref "U7") (pin "9") (pinfunction "LHPOUT_9") (pintype "output"))
    )
    (net (code "126") (name "unconnected-(U7-MICBIAS-Pad17)") (class "Default")
      (node (ref "U7") (pin "17") (pinfunction "MICBIAS_17") (pintype "output"))
    )
    (net (code "127") (name "unconnected-(U7-MICIN-Pad18)") (class "Default")
      (node (ref "U7") (pin "18") (pinfunction "MICIN_18") (pintype "input"))
    )
    (net (code "128") (name "unconnected-(U7-RHPOUT-Pad10)") (class "Default")
      (node (ref "U7") (pin "10") (pinfunction "RHPOUT_10") (pintype "output"))
    )
    (net (code "129") (name "unconnected-(U7-XTO-Pad26)") (class "Default")
      (node (ref "U7") (pin "26") (pinfunction "XTO_26") (pintype "output"))
    )
  )
)
